# esp-adap.net
KiCad netlist of a schematic drawn in EAGLE
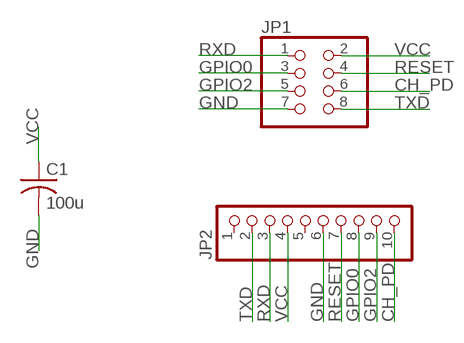
[diagram p0: schematic, sheet 1]

(export (version "E")
  (design (tool "Eeschema 10.0.6"))
  (components
    (comp (ref "C1")
      (value "100u")
      (footprint "eagle-import:C1206K")
      (libsource (lib "eagle-import") (part "C-USC1206K"))
    )
    (comp (ref "JP1")
      (value "PINHD-2X4")
      (footprint "eagle-import:2X04")
      (libsource (lib "eagle-import") (part "PINHD-2X4"))
    )
    (comp (ref "JP2")
      (value "PINHD-1X10")
      (footprint "eagle-import:1X10")
      (libsource (lib "eagle-import") (part "PINHD-1X10"))
    )
  )
  (nets
    (net (code "1") (name "/CH_PD") (class "Default")
      (node (ref "JP1") (pin "6") (pinfunction "6_6") (pintype "passive"))
      (node (ref "JP2") (pin "10") (pinfunction "10_10") (pintype "passive"))
    )
    (net (code "2") (name "/GND") (class "Default")
      (node (ref "C1") (pin "2") (pinfunction "2_2") (pintype "passive"))
      (node (ref "JP1") (pin "7") (pinfunction "7_7") (pintype "passive"))
      (node (ref "JP2") (pin "6") (pinfunction "6_6") (pintype "passive"))
    )
    (net (code "3") (name "/GPIO0") (class "Default")
      (node (ref "JP1") (pin "3") (pinfunction "3_3") (pintype "passive"))
      (node (ref "JP2") (pin "8") (pinfunction "8_8") (pintype "passive"))
    )
    (net (code "4") (name "/GPIO2") (class "Default")
      (node (ref "JP1") (pin "5") (pinfunction "5_5") (pintype "passive"))
      (node (ref "JP2") (pin "9") (pinfunction "9_9") (pintype "passive"))
    )
    (net (code "5") (name "/RESET") (class "Default")
      (node (ref "JP1") (pin "4") (pinfunction "4_4") (pintype "passive"))
      (node (ref "JP2") (pin "7") (pinfunction "7_7") (pintype "passive"))
    )
    (net (code "6") (name "/RXD") (class "Default")
      (node (ref "JP1") (pin "1") (pinfunction "1_1") (pintype "passive"))
      (node (ref "JP2") (pin "3") (pinfunction "3_3") (pintype "passive"))
    )
    (net (code "7") (name "/TXD") (class "Default")
      (node (ref "JP1") (pin "8") (pinfunction "8_8") (pintype "passive"))
      (node (ref "JP2") (pin "2") (pinfunction "2_2") (pintype "passive"))
    )
    (net (code "8") (name "/VCC") (class "Default")
      (node (ref "C1") (pin "1") (pinfunction "1_1") (pintype "passive"))
      (node (ref "JP1") (pin "2") (pinfunction "2_2") (pintype "passive"))
      (node (ref "JP2") (pin "4") (pinfunction "4_4") (pintype "passive"))
    )
    (net (code "9") (name "unconnected-(JP2-Pad1)") (class "Default")
      (node (ref "JP2") (pin "1") (pinfunction "1_1") (pintype "passive"))
    )
    (net (code "10") (name "unconnected-(JP2-Pad5)") (class "Default")
      (node (ref "JP2") (pin "5") (pinfunction "5_5") (pintype "passive"))
    )
  )
)
